# 23.net
KiCad netlist of a schematic drawn in Altium Designer
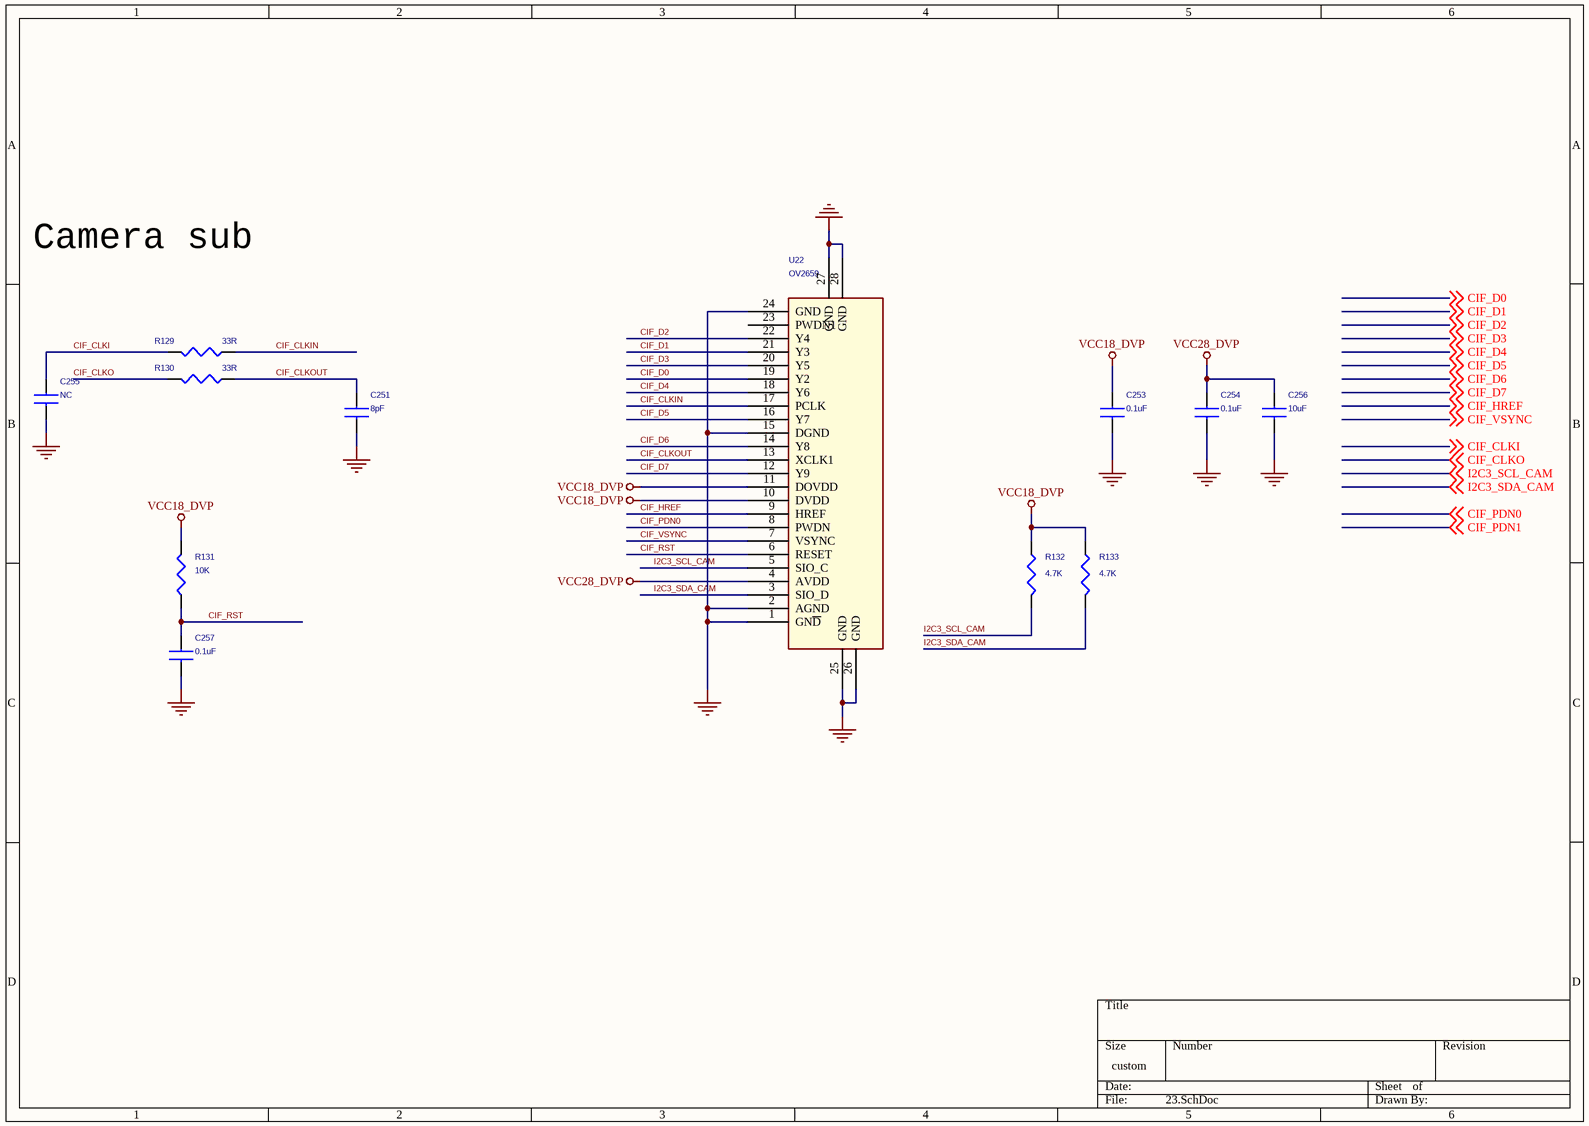
[diagram p0: 23.SchDoc]

(export (version "E")
  (design (tool "Eeschema 10.0.6"))
  (components
    (comp (ref "C251")
      (value "8pF")
      (footprint "C0603")
      (description "CAP,MLCC,8pF,+/-10%,NPO,6.3V,SMD0402")
      (libsource (lib "*") (part "CAP NP_Dup3"))
    )
    (comp (ref "C253") (value "0.1uF") (footprint "C0603") (libsource (lib "*") (part "CAP NP_Dup3")))
    (comp (ref "C254") (value "0.1uF") (footprint "C0603") (libsource (lib "*") (part "CAP NP_Dup3")))
    (comp (ref "C255")
      (value "NC")
      (footprint "C0603")
      (description "CAP,MLCC,8pF,+/-10%,NPO,6.3V,SMD0402")
      (libsource (lib "*") (part "CAP NP_Dup3"))
    )
    (comp (ref "C256") (value "10uF") (footprint "C0603") (libsource (lib "*") (part "CAP NP_Dup3")))
    (comp (ref "C257")
      (value "0.1uF")
      (footprint "C0603")
      (description "CAP,MLCC,100nF,+/-10%,X7R,6.3V,SMD0402")
      (libsource (lib "*") (part "CAP NP_Dup3"))
    )
    (comp (ref "R129")
      (value "33R")
      (footprint "r0402")
      (description "RES,thick film,22Ohm,+/-5%,1/16W,SMD0402")
      (libsource (lib "*") (part "RESISTOR_0_Dup1"))
    )
    (comp (ref "R130")
      (value "33R")
      (footprint "r0402")
      (description "RES,thick film,22Ohm,+/-5%,1/16W,SMD0402")
      (libsource (lib "*") (part "RESISTOR_0_Dup1"))
    )
    (comp (ref "R131")
      (value "10K")
      (footprint "r0402")
      (description "NC")
      (libsource (lib "*") (part "RESISTOR"))
    )
    (comp (ref "R132") (value "4.7K") (footprint "r0402") (libsource (lib "*") (part "RESISTOR_0_Dup3")))
    (comp (ref "R133") (value "4.7K") (footprint "r0402") (libsource (lib "*") (part "RESISTOR_0_Dup3")))
    (comp (ref "U22") (value "OV2659") (footprint "AXT524124") (libsource (lib "*") (part "LCM0200CE1A0_0")))
  )
  (nets
    (net (code "1") (name "/CIF_CLKIN") (class "Default")
      (node (ref "R129") (pin "1") (pinfunction "1_1") (pintype "passive"))
      (node (ref "U22") (pin "17") (pinfunction "PCLK_17") (pintype "passive"))
    )
    (net (code "2") (name "/CIF_CLKOUT") (class "Default")
      (node (ref "C251") (pin "2") (pinfunction "2_2") (pintype "passive"))
      (node (ref "R130") (pin "1") (pinfunction "1_1") (pintype "passive"))
      (node (ref "U22") (pin "13") (pinfunction "XCLK1_13") (pintype "passive"))
    )
    (net (code "3") (name "/CIF_RST") (class "Default")
      (node (ref "C257") (pin "2") (pinfunction "2_2") (pintype "passive"))
      (node (ref "R131") (pin "1") (pinfunction "1_1") (pintype "passive"))
      (node (ref "U22") (pin "6") (pinfunction "RESET_6") (pintype "passive"))
    )
    (net (code "4") (name "CIF_CLKI") (class "Default")
      (node (ref "C255") (pin "2") (pinfunction "2_2") (pintype "passive"))
      (node (ref "R129") (pin "2") (pinfunction "2_2") (pintype "passive"))
    )
    (net (code "5") (name "CIF_CLKO") (class "Default")
      (node (ref "R130") (pin "2") (pinfunction "2_2") (pintype "passive"))
    )
    (net (code "6") (name "CIF_D0") (class "Default")
      (node (ref "U22") (pin "19") (pinfunction "Y2_19") (pintype "passive"))
    )
    (net (code "7") (name "CIF_D1") (class "Default")
      (node (ref "U22") (pin "21") (pinfunction "Y3_21") (pintype "passive"))
    )
    (net (code "8") (name "CIF_D2") (class "Default")
      (node (ref "U22") (pin "22") (pinfunction "Y4_22") (pintype "passive"))
    )
    (net (code "9") (name "CIF_D3") (class "Default")
      (node (ref "U22") (pin "20") (pinfunction "Y5_20") (pintype "passive"))
    )
    (net (code "10") (name "CIF_D4") (class "Default")
      (node (ref "U22") (pin "18") (pinfunction "Y6_18") (pintype "passive"))
    )
    (net (code "11") (name "CIF_D5") (class "Default")
      (node (ref "U22") (pin "16") (pinfunction "Y7_16") (pintype "passive"))
    )
    (net (code "12") (name "CIF_D6") (class "Default")
      (node (ref "U22") (pin "14") (pinfunction "Y8_14") (pintype "passive"))
    )
    (net (code "13") (name "CIF_D7") (class "Default")
      (node (ref "U22") (pin "12") (pinfunction "Y9_12") (pintype "passive"))
    )
    (net (code "14") (name "CIF_HREF") (class "Default")
      (node (ref "U22") (pin "9") (pinfunction "HREF_9") (pintype "passive"))
    )
    (net (code "15") (name "CIF_PDN0") (class "Default")
      (node (ref "U22") (pin "8") (pinfunction "PWDN_8") (pintype "passive"))
    )
    (net (code "17") (name "CIF_VSYNC") (class "Default")
      (node (ref "U22") (pin "7") (pinfunction "VSYNC_7") (pintype "passive"))
    )
    (net (code "18") (name "GND") (class "Default")
      (node (ref "C251") (pin "1") (pinfunction "1_1") (pintype "passive"))
      (node (ref "C253") (pin "1") (pinfunction "1_1") (pintype "passive"))
      (node (ref "C254") (pin "1") (pinfunction "1_1") (pintype "passive"))
      (node (ref "C255") (pin "1") (pinfunction "1_1") (pintype "passive"))
      (node (ref "C256") (pin "1") (pinfunction "1_1") (pintype "passive"))
      (node (ref "C257") (pin "1") (pinfunction "1_1") (pintype "passive"))
      (node (ref "U22") (pin "1") (pinfunction "GN~{D}_1") (pintype "power_in"))
      (node (ref "U22") (pin "15") (pinfunction "DGND_15") (pintype "passive"))
      (node (ref "U22") (pin "2") (pinfunction "AGND_2") (pintype "passive"))
      (node (ref "U22") (pin "24") (pinfunction "GND_24") (pintype "power_in"))
      (node (ref "U22") (pin "25") (pinfunction "GND_25") (pintype "power_in"))
      (node (ref "U22") (pin "26") (pinfunction "GND_26") (pintype "power_in"))
      (node (ref "U22") (pin "27") (pinfunction "GND_27") (pintype "power_in"))
      (node (ref "U22") (pin "28") (pinfunction "GND_28") (pintype "power_in"))
    )
    (net (code "19") (name "I2C3_SCL_CAM") (class "Default")
      (node (ref "R132") (pin "2") (pinfunction "2_2") (pintype "passive"))
      (node (ref "U22") (pin "5") (pinfunction "SIO_C_5") (pintype "passive"))
    )
    (net (code "20") (name "I2C3_SDA_CAM") (class "Default")
      (node (ref "R133") (pin "2") (pinfunction "2_2") (pintype "passive"))
      (node (ref "U22") (pin "3") (pinfunction "SIO_D_3") (pintype "passive"))
    )
    (net (code "21") (name "VCC18_DVP") (class "Default")
      (node (ref "C253") (pin "2") (pinfunction "2_2") (pintype "passive"))
      (node (ref "R131") (pin "2") (pinfunction "2_2") (pintype "passive"))
      (node (ref "R132") (pin "1") (pinfunction "1_1") (pintype "passive"))
      (node (ref "R133") (pin "1") (pinfunction "1_1") (pintype "passive"))
      (node (ref "U22") (pin "10") (pinfunction "DVDD_10") (pintype "passive"))
      (node (ref "U22") (pin "11") (pinfunction "DOVDD_11") (pintype "passive"))
    )
    (net (code "22") (name "VCC28_DVP") (class "Default")
      (node (ref "C254") (pin "2") (pinfunction "2_2") (pintype "passive"))
      (node (ref "C256") (pin "2") (pinfunction "2_2") (pintype "passive"))
      (node (ref "U22") (pin "4") (pinfunction "AVDD_4") (pintype "passive"))
    )
    (net (code "23") (name "unconnected-(U22-PWDN1-Pad23)") (class "Default")
      (node (ref "U22") (pin "23") (pinfunction "PWDN1_23") (pintype "passive"))
    )
  )
)
